# Slave_Micro.net
KiCad netlist of a schematic drawn in Altium Designer
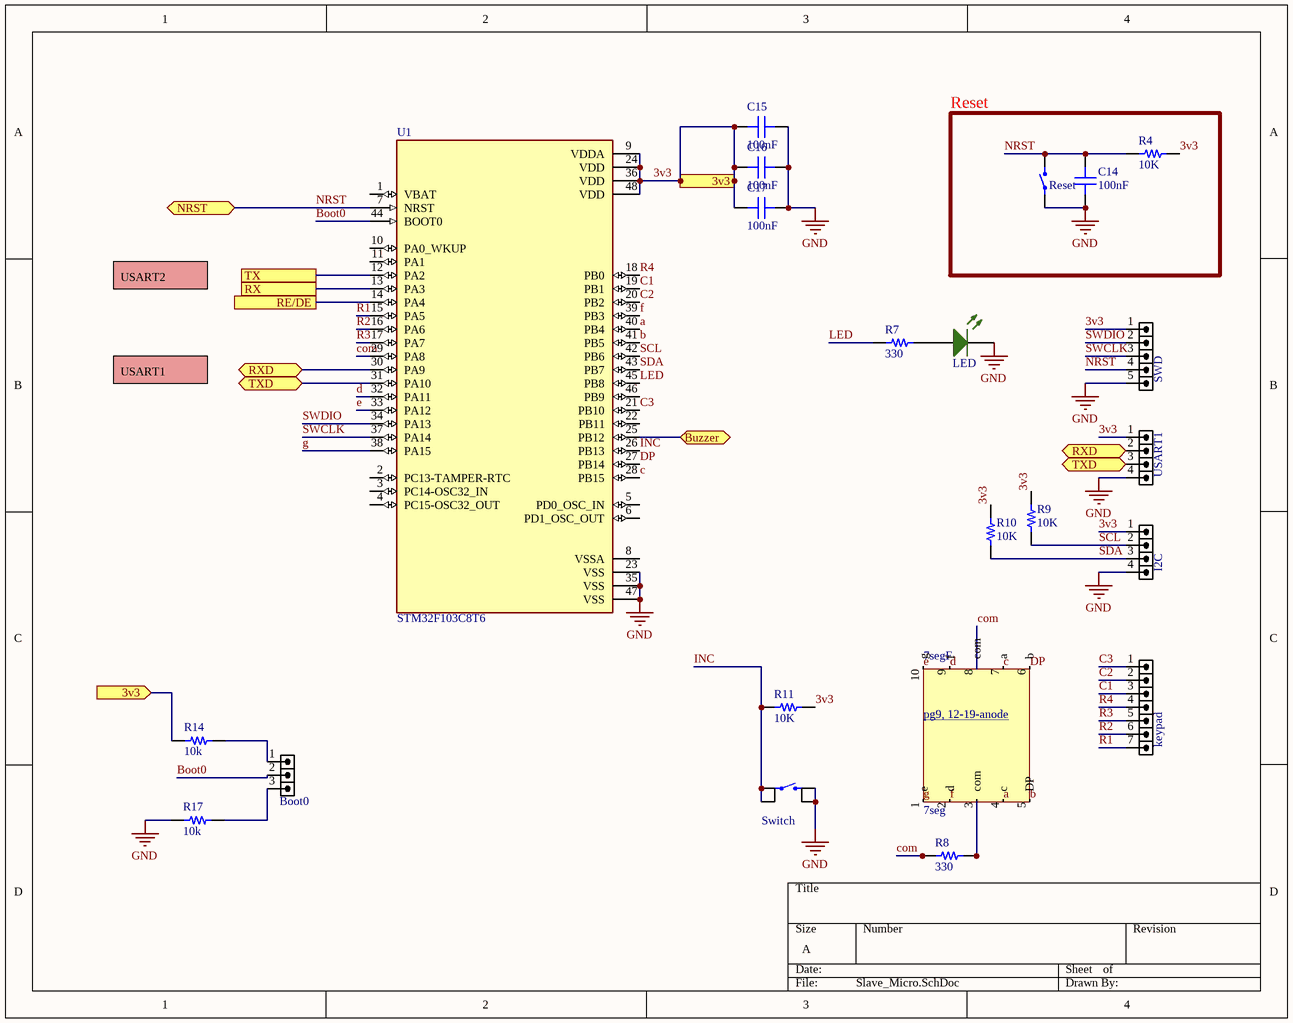
[diagram p0: Slave_Micro.SchDoc]

(export (version "E")
  (design (tool "Eeschema 10.0.6"))
  (components
    (comp (ref "7seg")
      (value "7seg")
      (footprint "7seg 12x19")
      (description "file:///C:/Users/Tamana/Downloads/7SEG-12-19mm-GREEN-ANOD.pdf")
      (libsource (lib "7seg") (part "7seg"))
    )
    (comp (ref "Boot0")
      (value "HDRM3")
      (footprint "HDR_1X3")
      (description "CONN, HEADER, Male, pitch: 2.54mm, 3POS")
      (libsource (lib "Conn Header") (part "HDR_1X3"))
    )
    (comp (ref "C14")
      (value "100nF")
      (footprint "CAP 0805_2012")
      (description "SMT Capacitor")
      (libsource (lib "Capacitor") (part "Cap 0805"))
    )
    (comp (ref "C15")
      (value "100nF")
      (footprint "CAP 0805_2012")
      (description "SMT Capacitor")
      (libsource (lib "Capacitor") (part "Cap 0805"))
    )
    (comp (ref "C16")
      (value "100nF")
      (footprint "CAP 0805_2012")
      (description "SMT Capacitor")
      (libsource (lib "Capacitor") (part "Cap 0805"))
    )
    (comp (ref "C17")
      (value "100nF")
      (footprint "CAP 0805_2012")
      (description "SMT Capacitor")
      (libsource (lib "Capacitor") (part "Cap 0805"))
    )
    (comp (ref "I2C")
      (value "HDR1X4")
      (footprint "HDR_1X4")
      (description "CONN, HEADER, Male, pitch: 2.54mm, 4POS")
      (libsource (lib "Conn Header") (part "HDR_1X4"))
    )
    (comp (ref "keypad")
      (value "HDR1X7")
      (footprint "HDR_1X7")
      (description "CONN, HEADER, Male, pitch: 2.54mm, 7POS")
      (libsource (lib "Conn Header") (part "HDR_1X7"))
    )
    (comp (ref "LED")
      (value "LED SMD 0805 GREEN")
      (footprint "LED_0805_GREEN")
      (libsource (lib "Led") (part "LED SMD 0805 GREEN"))
    )
    (comp (ref "R4")
      (value "10K")
      (footprint "RES 0805_2012")
      (description "SMT Resistor")
      (libsource (lib "Resistor") (part "Res 0805"))
    )
    (comp (ref "R7")
      (value "330")
      (footprint "RES 0805_2012")
      (description "SMT Resistor")
      (libsource (lib "Resistor") (part "Res 0805"))
    )
    (comp (ref "R8")
      (value "330")
      (footprint "RES 0805_2012")
      (description "SMT Resistor")
      (libsource (lib "Resistor") (part "Res 0805"))
    )
    (comp (ref "R9")
      (value "10K")
      (footprint "RES 0805_2012")
      (description "SMT Resistor")
      (libsource (lib "Resistor") (part "Res 0805"))
    )
    (comp (ref "R10")
      (value "10K")
      (footprint "RES 0805_2012")
      (description "SMT Resistor")
      (libsource (lib "Resistor") (part "Res 0805"))
    )
    (comp (ref "R11")
      (value "10K")
      (footprint "RES 0805_2012")
      (description "SMT Resistor")
      (libsource (lib "Resistor") (part "Res 0805"))
    )
    (comp (ref "R14")
      (value "10k")
      (footprint "RES 0805_2012")
      (description "SMT Resistor")
      (libsource (lib "Resistor") (part "Res 0805"))
    )
    (comp (ref "R17")
      (value "10k")
      (footprint "RES 0805_2012")
      (description "SMT Resistor")
      (libsource (lib "Resistor") (part "Res 0805"))
    )
    (comp (ref "Reset")
      (value "Tactile 2PIN 6X3.5mm H4.57mm (SMD)")
      (footprint "SWPBS_SPST_6X3X5")
      (description "Tactile Switch SPST-NO Top Actuated Surface Mount")
      (fields (field (name "PARTNUMBER") "FSMSMTR-ND"))
      (libsource (lib "Switch") (part "Tactile 2PIN 6X3.5mm H4.57mm (SMD)"))
    )
    (comp (ref "SWD")
      (value "HDR1X5")
      (footprint "HDR_1X5")
      (description "CONN, HEADER, Male, pitch: 2.54mm, 5POS")
      (libsource (lib "Conn Header") (part "HDR_1X5"))
    )
    (comp (ref "Switch")
      (value "Tactile 4PIN 6X6mm H5mm (THD)")
      (footprint "SWPBT_SPDT_6X6X5SKHH")
      (description "Tactile Switch SPST-NO Top Actuated Surface Mount")
      (fields (field (name "PARTNUMBER") "PTS645SH50SMTR92 LFS"))
      (libsource (lib "Switch") (part "Tactile 4PIN 6X6mm H5mm (THD)"))
    )
    (comp (ref "U1")
      (value "STM32F103C8T6")
      (footprint "QFP50P900X900X160-48N")
      (description "ARM® Cortex®-M3 STM32F1 Microcontroller IC 32-Bit 72MHz 64KB (64K x 8) FLASH 48-LQFP (7x7)")
      (fields (field (name "MF") "STMicroelectronics"))
      (libsource (lib "STM32F103C8T6") (part "STM32F103C8T6"))
    )
    (comp (ref "USART1")
      (value "HDR1X4")
      (footprint "HDR_1X4")
      (description "CONN, HEADER, Male, pitch: 2.54mm, 4POS")
      (libsource (lib "Conn Header") (part "HDR_1X4"))
    )
  )
  (nets
    (net (code "1") (name "/3v3") (class "Default")
      (node (ref "C15") (pin "2") (pinfunction "2_2") (pintype "passive"))
      (node (ref "C16") (pin "2") (pinfunction "2_2") (pintype "passive"))
      (node (ref "C17") (pin "2") (pinfunction "2_2") (pintype "passive"))
      (node (ref "I2C") (pin "1") (pinfunction "1_1") (pintype "passive"))
      (node (ref "R10") (pin "2") (pinfunction "2_2") (pintype "passive"))
      (node (ref "R11") (pin "2") (pinfunction "2_2") (pintype "passive"))
      (node (ref "R14") (pin "1") (pinfunction "1_1") (pintype "passive"))
      (node (ref "R4") (pin "2") (pinfunction "2_2") (pintype "passive"))
      (node (ref "R9") (pin "2") (pinfunction "2_2") (pintype "passive"))
      (node (ref "SWD") (pin "1") (pinfunction "1_1") (pintype "passive"))
      (node (ref "U1") (pin "24") (pinfunction "VDD_24") (pintype "power_in"))
      (node (ref "U1") (pin "36") (pinfunction "VDD_36") (pintype "power_in"))
      (node (ref "U1") (pin "48") (pinfunction "VDD_48") (pintype "power_in"))
      (node (ref "U1") (pin "9") (pinfunction "VDDA_9") (pintype "power_in"))
      (node (ref "USART1") (pin "1") (pinfunction "1_1") (pintype "passive"))
    )
    (net (code "2") (name "/Boot0") (class "Default")
      (node (ref "Boot0") (pin "2") (pinfunction "2_2") (pintype "passive"))
      (node (ref "U1") (pin "44") (pinfunction "BOOT0_44") (pintype "input"))
    )
    (net (code "3") (name "/Buzzer") (class "Default")
      (node (ref "U1") (pin "25") (pinfunction "PB12_25") (pintype "bidirectional"))
    )
    (net (code "4") (name "/C1") (class "Default")
      (node (ref "U1") (pin "19") (pinfunction "PB1_19") (pintype "bidirectional"))
      (node (ref "keypad") (pin "3") (pinfunction "3_3") (pintype "passive"))
    )
    (net (code "5") (name "/C2") (class "Default")
      (node (ref "U1") (pin "20") (pinfunction "PB2_20") (pintype "bidirectional"))
      (node (ref "keypad") (pin "2") (pinfunction "2_2") (pintype "passive"))
    )
    (net (code "6") (name "/C3") (class "Default")
      (node (ref "U1") (pin "21") (pinfunction "PB10_21") (pintype "bidirectional"))
      (node (ref "keypad") (pin "1") (pinfunction "1_1") (pintype "passive"))
    )
    (net (code "7") (name "/DP") (class "Default")
      (node (ref "7seg") (pin "6") (pinfunction "b_6") (pintype "passive"))
      (node (ref "U1") (pin "27") (pinfunction "PB14_27") (pintype "bidirectional"))
    )
    (net (code "8") (name "/INC") (class "Default")
      (node (ref "R11") (pin "1") (pinfunction "1_1") (pintype "passive"))
      (node (ref "Switch") (pin "1") (pinfunction "1_1") (pintype "passive"))
      (node (ref "Switch") (pin "4") (pinfunction "4_4") (pintype "passive"))
      (node (ref "U1") (pin "26") (pinfunction "PB13_26") (pintype "bidirectional"))
    )
    (net (code "9") (name "/LED") (class "Default")
      (node (ref "R7") (pin "1") (pinfunction "1_1") (pintype "passive"))
      (node (ref "U1") (pin "45") (pinfunction "PB8_45") (pintype "bidirectional"))
    )
    (net (code "10") (name "/NRST") (class "Default")
      (node (ref "C14") (pin "2") (pinfunction "2_2") (pintype "passive"))
      (node (ref "R4") (pin "1") (pinfunction "1_1") (pintype "passive"))
      (node (ref "Reset") (pin "2") (pinfunction "2_2") (pintype "passive"))
      (node (ref "SWD") (pin "4") (pinfunction "4_4") (pintype "passive"))
      (node (ref "U1") (pin "7") (pinfunction "NRST_7") (pintype "input"))
    )
    (net (code "11") (name "/R1") (class "Default")
      (node (ref "U1") (pin "15") (pinfunction "PA5_15") (pintype "bidirectional"))
      (node (ref "keypad") (pin "7") (pinfunction "7_7") (pintype "passive"))
    )
    (net (code "12") (name "/R2") (class "Default")
      (node (ref "U1") (pin "16") (pinfunction "PA6_16") (pintype "bidirectional"))
      (node (ref "keypad") (pin "6") (pinfunction "6_6") (pintype "passive"))
    )
    (net (code "13") (name "/R3") (class "Default")
      (node (ref "U1") (pin "17") (pinfunction "PA7_17") (pintype "bidirectional"))
      (node (ref "keypad") (pin "5") (pinfunction "5_5") (pintype "passive"))
    )
    (net (code "14") (name "/R4") (class "Default")
      (node (ref "U1") (pin "18") (pinfunction "PB0_18") (pintype "bidirectional"))
      (node (ref "keypad") (pin "4") (pinfunction "4_4") (pintype "passive"))
    )
    (net (code "15") (name "/RE{slash}DE") (class "Default")
      (node (ref "U1") (pin "14") (pinfunction "PA4_14") (pintype "bidirectional"))
    )
    (net (code "16") (name "/RX") (class "Default")
      (node (ref "U1") (pin "13") (pinfunction "PA3_13") (pintype "bidirectional"))
    )
    (net (code "17") (name "/RXD") (class "Default")
      (node (ref "U1") (pin "30") (pinfunction "PA9_30") (pintype "bidirectional"))
      (node (ref "USART1") (pin "2") (pinfunction "2_2") (pintype "passive"))
    )
    (net (code "18") (name "/SCL") (class "Default")
      (node (ref "I2C") (pin "2") (pinfunction "2_2") (pintype "passive"))
      (node (ref "R9") (pin "1") (pinfunction "1_1") (pintype "passive"))
      (node (ref "U1") (pin "42") (pinfunction "PB6_42") (pintype "bidirectional"))
    )
    (net (code "19") (name "/SDA") (class "Default")
      (node (ref "I2C") (pin "3") (pinfunction "3_3") (pintype "passive"))
      (node (ref "R10") (pin "1") (pinfunction "1_1") (pintype "passive"))
      (node (ref "U1") (pin "43") (pinfunction "PB7_43") (pintype "bidirectional"))
    )
    (net (code "20") (name "/SWCLK") (class "Default")
      (node (ref "SWD") (pin "3") (pinfunction "3_3") (pintype "passive"))
      (node (ref "U1") (pin "37") (pinfunction "PA14_37") (pintype "bidirectional"))
    )
    (net (code "21") (name "/SWDIO") (class "Default")
      (node (ref "SWD") (pin "2") (pinfunction "2_2") (pintype "passive"))
      (node (ref "U1") (pin "34") (pinfunction "PA13_34") (pintype "bidirectional"))
    )
    (net (code "22") (name "/TX") (class "Default")
      (node (ref "U1") (pin "12") (pinfunction "PA2_12") (pintype "bidirectional"))
    )
    (net (code "23") (name "/TXD") (class "Default")
      (node (ref "U1") (pin "31") (pinfunction "PA10_31") (pintype "bidirectional"))
      (node (ref "USART1") (pin "3") (pinfunction "3_3") (pintype "passive"))
    )
    (net (code "24") (name "/a") (class "Default")
      (node (ref "7seg") (pin "4") (pinfunction "c_4") (pintype "passive"))
      (node (ref "U1") (pin "40") (pinfunction "PB4_40") (pintype "bidirectional"))
    )
    (net (code "25") (name "/b") (class "Default")
      (node (ref "7seg") (pin "5") (pinfunction "DP_5") (pintype "passive"))
      (node (ref "U1") (pin "41") (pinfunction "PB5_41") (pintype "bidirectional"))
    )
    (net (code "26") (name "/c") (class "Default")
      (node (ref "7seg") (pin "7") (pinfunction "a_7") (pintype "passive"))
      (node (ref "U1") (pin "28") (pinfunction "PB15_28") (pintype "bidirectional"))
    )
    (net (code "27") (name "/com") (class "Default")
      (node (ref "7seg") (pin "8") (pinfunction "com_8") (pintype "passive"))
      (node (ref "R8") (pin "1") (pinfunction "1_1") (pintype "passive"))
      (node (ref "U1") (pin "29") (pinfunction "PA8_29") (pintype "bidirectional"))
    )
    (net (code "28") (name "/d") (class "Default")
      (node (ref "7seg") (pin "9") (pinfunction "f_9") (pintype "passive"))
      (node (ref "U1") (pin "32") (pinfunction "PA11_32") (pintype "bidirectional"))
    )
    (net (code "29") (name "/e") (class "Default")
      (node (ref "7seg") (pin "10") (pinfunction "g_10") (pintype "passive"))
      (node (ref "U1") (pin "33") (pinfunction "PA12_33") (pintype "bidirectional"))
    )
    (net (code "30") (name "/f") (class "Default")
      (node (ref "7seg") (pin "2") (pinfunction "d_2") (pintype "passive"))
      (node (ref "U1") (pin "39") (pinfunction "PB3_39") (pintype "bidirectional"))
    )
    (net (code "31") (name "/g") (class "Default")
      (node (ref "7seg") (pin "1") (pinfunction "e_1") (pintype "passive"))
      (node (ref "U1") (pin "38") (pinfunction "PA15_38") (pintype "bidirectional"))
    )
    (net (code "32") (name "GND") (class "Default")
      (node (ref "C14") (pin "1") (pinfunction "1_1") (pintype "passive"))
      (node (ref "C15") (pin "1") (pinfunction "1_1") (pintype "passive"))
      (node (ref "C16") (pin "1") (pinfunction "1_1") (pintype "passive"))
      (node (ref "C17") (pin "1") (pinfunction "1_1") (pintype "passive"))
      (node (ref "I2C") (pin "4") (pinfunction "4_4") (pintype "passive"))
      (node (ref "LED") (pin "2") (pinfunction "K_2") (pintype "passive"))
      (node (ref "R17") (pin "1") (pinfunction "1_1") (pintype "passive"))
      (node (ref "Reset") (pin "1") (pinfunction "1_1") (pintype "passive"))
      (node (ref "SWD") (pin "5") (pinfunction "5_5") (pintype "passive"))
      (node (ref "Switch") (pin "2") (pinfunction "2_2") (pintype "passive"))
      (node (ref "Switch") (pin "3") (pinfunction "3_3") (pintype "passive"))
      (node (ref "U1") (pin "23") (pinfunction "VSS_23") (pintype "power_in"))
      (node (ref "U1") (pin "35") (pinfunction "VSS_35") (pintype "power_in"))
      (node (ref "U1") (pin "47") (pinfunction "VSS_47") (pintype "power_in"))
      (node (ref "USART1") (pin "4") (pinfunction "4_4") (pintype "passive"))
    )
    (net (code "33") (name "Net-(7segF-com-Pad3)") (class "Default")
      (node (ref "7seg") (pin "3") (pinfunction "com_3") (pintype "passive"))
      (node (ref "R8") (pin "2") (pinfunction "2_2") (pintype "passive"))
    )
    (net (code "34") (name "Net-(Boot0-Pad1)") (class "Default")
      (node (ref "Boot0") (pin "1") (pinfunction "1_1") (pintype "passive"))
      (node (ref "R14") (pin "2") (pinfunction "2_2") (pintype "passive"))
    )
    (net (code "35") (name "Net-(Boot0-Pad3)") (class "Default")
      (node (ref "Boot0") (pin "3") (pinfunction "3_3") (pintype "passive"))
      (node (ref "R17") (pin "2") (pinfunction "2_2") (pintype "passive"))
    )
    (net (code "36") (name "Net-(LED-A)") (class "Default")
      (node (ref "LED") (pin "1") (pinfunction "A_1") (pintype "passive"))
      (node (ref "R7") (pin "2") (pinfunction "2_2") (pintype "passive"))
    )
    (net (code "37") (name "unconnected-(U1-PA0_WKUP-Pad10)") (class "Default")
      (node (ref "U1") (pin "10") (pinfunction "PA0_WKUP_10") (pintype "bidirectional"))
    )
    (net (code "38") (name "unconnected-(U1-PA1-Pad11)") (class "Default")
      (node (ref "U1") (pin "11") (pinfunction "PA1_11") (pintype "bidirectional"))
    )
    (net (code "39") (name "unconnected-(U1-PB9-Pad46)") (class "Default")
      (node (ref "U1") (pin "46") (pinfunction "PB9_46") (pintype "bidirectional"))
    )
    (net (code "40") (name "unconnected-(U1-PB11-Pad22)") (class "Default")
      (node (ref "U1") (pin "22") (pinfunction "PB11_22") (pintype "bidirectional"))
    )
    (net (code "41") (name "unconnected-(U1-PC13-TAMPER-RTC-Pad2)") (class "Default")
      (node (ref "U1") (pin "2") (pinfunction "PC13-TAMPER-RTC_2") (pintype "bidirectional"))
    )
    (net (code "42") (name "unconnected-(U1-PC14-OSC32_IN-Pad3)") (class "Default")
      (node (ref "U1") (pin "3") (pinfunction "PC14-OSC32_IN_3") (pintype "bidirectional"))
    )
    (net (code "43") (name "unconnected-(U1-PC15-OSC32_OUT-Pad4)") (class "Default")
      (node (ref "U1") (pin "4") (pinfunction "PC15-OSC32_OUT_4") (pintype "bidirectional"))
    )
    (net (code "44") (name "unconnected-(U1-PD0_OSC_IN-Pad5)") (class "Default")
      (node (ref "U1") (pin "5") (pinfunction "PD0_OSC_IN_5") (pintype "bidirectional"))
    )
    (net (code "45") (name "unconnected-(U1-PD1_OSC_OUT-Pad6)") (class "Default")
      (node (ref "U1") (pin "6") (pinfunction "PD1_OSC_OUT_6") (pintype "bidirectional"))
    )
    (net (code "46") (name "unconnected-(U1-VBAT-Pad1)") (class "Default")
      (node (ref "U1") (pin "1") (pinfunction "VBAT_1") (pintype "bidirectional"))
    )
    (net (code "47") (name "unconnected-(U1-VSSA-Pad8)") (class "Default")
      (node (ref "U1") (pin "8") (pinfunction "VSSA_8") (pintype "power_in"))
    )
  )
)
